# Feather_32U4_Servo_Board_V1_1.net
KiCad netlist of a schematic drawn in EAGLE
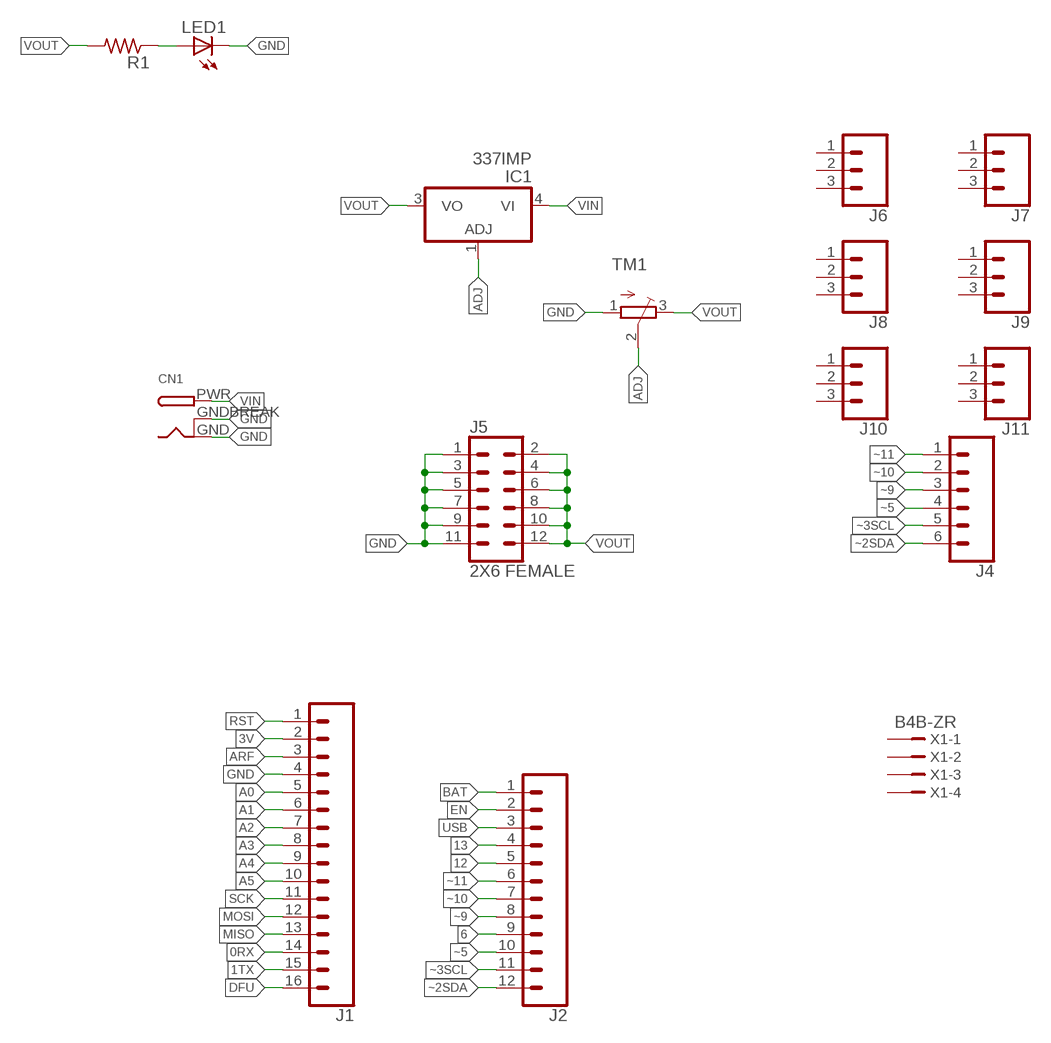
[diagram p0: schematic, sheet 1]

(export (version "E")
  (design (tool "Eeschema 10.0.6"))
  (components
    (comp (ref "CN1")
      (value "DCBARRELPTH")
      (footprint "eagle-import:DCJACK_2MM_PTH")
      (libsource (lib "eagle-import") (part "DCBARRELPTH"))
    )
    (comp (ref "IC1")
      (value "337IMP")
      (footprint "eagle-import:SOT223")
      (libsource (lib "eagle-import") (part "337IMP"))
    )
    (comp (ref "J1")
      (value "CONN_16")
      (footprint "eagle-import:1X16")
      (libsource (lib "eagle-import") (part "CONN_16"))
    )
    (comp (ref "J2")
      (value "CONN_12")
      (footprint "eagle-import:1X12")
      (libsource (lib "eagle-import") (part "CONN_12"))
    )
    (comp (ref "J4")
      (value "CONN_06SILK_FEMALE_PTH")
      (footprint "eagle-import:1X06")
      (libsource (lib "eagle-import") (part "CONN_06SILK_FEMALE_PTH"))
    )
    (comp (ref "J5")
      (value "2X6 FEMALE")
      (footprint "eagle-import:2X6")
      (libsource (lib "eagle-import") (part "CONN_06X2PTH_FEMALE"))
    )
    (comp (ref "J6")
      (value "CONN_03POLAR")
      (footprint "eagle-import:MOLEX-1X3")
      (libsource (lib "eagle-import") (part "CONN_03POLAR"))
    )
    (comp (ref "J7")
      (value "CONN_03POLAR")
      (footprint "eagle-import:MOLEX-1X3")
      (libsource (lib "eagle-import") (part "CONN_03POLAR"))
    )
    (comp (ref "J8")
      (value "CONN_03POLAR")
      (footprint "eagle-import:MOLEX-1X3")
      (libsource (lib "eagle-import") (part "CONN_03POLAR"))
    )
    (comp (ref "J9")
      (value "CONN_03POLAR")
      (footprint "eagle-import:MOLEX-1X3")
      (libsource (lib "eagle-import") (part "CONN_03POLAR"))
    )
    (comp (ref "J10")
      (value "CONN_03POLAR")
      (footprint "eagle-import:MOLEX-1X3")
      (libsource (lib "eagle-import") (part "CONN_03POLAR"))
    )
    (comp (ref "J11")
      (value "CONN_03POLAR")
      (footprint "eagle-import:MOLEX-1X3")
      (libsource (lib "eagle-import") (part "CONN_03POLAR"))
    )
    (comp (ref "LED1")
      (value "LEDCHIPLED_0805")
      (footprint "eagle-import:CHIPLED_0805")
      (libsource (lib "eagle-import") (part "LEDCHIPLED_0805"))
    )
    (comp (ref "R1")
      (value "R-US_M0805")
      (footprint "eagle-import:M0805")
      (libsource (lib "eagle-import") (part "R-US_M0805"))
    )
    (comp (ref "TM1")
      (value "TRIMPOTTC33X")
      (footprint "eagle-import:TC33X")
      (libsource (lib "eagle-import") (part "TRIMPOTTC33X"))
    )
    (comp (ref "X1")
      (value "B4B-ZR")
      (footprint "eagle-import:B4B-ZR")
      (libsource (lib "eagle-import") (part "?4B-ZRB"))
    )
  )
  (nets
    (net (code "1") (name "/~{2SDA}") (class "Default")
      (node (ref "J2") (pin "12") (pinfunction "12_12") (pintype "passive"))
      (node (ref "J4") (pin "6") (pinfunction "6_6") (pintype "passive"))
    )
    (net (code "2") (name "/~{3SCL}") (class "Default")
      (node (ref "J2") (pin "11") (pinfunction "11_11") (pintype "passive"))
      (node (ref "J4") (pin "5") (pinfunction "5_5") (pintype "passive"))
    )
    (net (code "3") (name "/~{5}") (class "Default")
      (node (ref "J2") (pin "10") (pinfunction "10_10") (pintype "passive"))
      (node (ref "J4") (pin "4") (pinfunction "4_4") (pintype "passive"))
    )
    (net (code "4") (name "/~{9}") (class "Default")
      (node (ref "J2") (pin "8") (pinfunction "8_8") (pintype "passive"))
      (node (ref "J4") (pin "3") (pinfunction "3_3") (pintype "passive"))
    )
    (net (code "5") (name "/~{10}") (class "Default")
      (node (ref "J2") (pin "7") (pinfunction "7_7") (pintype "passive"))
      (node (ref "J4") (pin "2") (pinfunction "2_2") (pintype "passive"))
    )
    (net (code "6") (name "/~{11}") (class "Default")
      (node (ref "J2") (pin "6") (pinfunction "6_6") (pintype "passive"))
      (node (ref "J4") (pin "1") (pinfunction "1_1") (pintype "passive"))
    )
    (net (code "7") (name "0RX") (class "Default")
      (node (ref "J1") (pin "14") (pinfunction "14_14") (pintype "passive"))
    )
    (net (code "8") (name "1TX") (class "Default")
      (node (ref "J1") (pin "15") (pinfunction "15_15") (pintype "passive"))
    )
    (net (code "9") (name "3V") (class "Default")
      (node (ref "J1") (pin "2") (pinfunction "2_2") (pintype "passive"))
    )
    (net (code "10") (name "6") (class "Default")
      (node (ref "J2") (pin "9") (pinfunction "9_9") (pintype "passive"))
    )
    (net (code "11") (name "12") (class "Default")
      (node (ref "J2") (pin "5") (pinfunction "5_5") (pintype "passive"))
    )
    (net (code "12") (name "13") (class "Default")
      (node (ref "J2") (pin "4") (pinfunction "4_4") (pintype "passive"))
    )
    (net (code "13") (name "A0") (class "Default")
      (node (ref "J1") (pin "5") (pinfunction "5_5") (pintype "passive"))
    )
    (net (code "14") (name "A1") (class "Default")
      (node (ref "J1") (pin "6") (pinfunction "6_6") (pintype "passive"))
    )
    (net (code "15") (name "A2") (class "Default")
      (node (ref "J1") (pin "7") (pinfunction "7_7") (pintype "passive"))
    )
    (net (code "16") (name "A3") (class "Default")
      (node (ref "J1") (pin "8") (pinfunction "8_8") (pintype "passive"))
    )
    (net (code "17") (name "A4") (class "Default")
      (node (ref "J1") (pin "9") (pinfunction "9_9") (pintype "passive"))
    )
    (net (code "18") (name "A5") (class "Default")
      (node (ref "J1") (pin "10") (pinfunction "10_10") (pintype "passive"))
    )
    (net (code "19") (name "ADJ") (class "Default")
      (node (ref "IC1") (pin "1") (pinfunction "ADJ_1") (pintype "input"))
      (node (ref "TM1") (pin "2") (pinfunction "S_2") (pintype "passive"))
    )
    (net (code "20") (name "ARF") (class "Default")
      (node (ref "J1") (pin "3") (pinfunction "3_3") (pintype "passive"))
    )
    (net (code "21") (name "BAT") (class "Default")
      (node (ref "J2") (pin "1") (pinfunction "1_1") (pintype "passive"))
    )
    (net (code "22") (name "DFU") (class "Default")
      (node (ref "J1") (pin "16") (pinfunction "16_16") (pintype "passive"))
    )
    (net (code "23") (name "EN") (class "Default")
      (node (ref "J2") (pin "2") (pinfunction "2_2") (pintype "passive"))
    )
    (net (code "24") (name "GND") (class "Default")
      (node (ref "CN1") (pin "GND") (pinfunction "GND_GND") (pintype "power_in"))
      (node (ref "CN1") (pin "GNDBREAK") (pinfunction "GNDBREAK_GNDBREAK") (pintype "power_in"))
      (node (ref "J1") (pin "4") (pinfunction "4_4") (pintype "passive"))
      (node (ref "J5") (pin "1") (pinfunction "1_1") (pintype "passive"))
      (node (ref "J5") (pin "11") (pinfunction "11_11") (pintype "passive"))
      (node (ref "J5") (pin "3") (pinfunction "3_3") (pintype "passive"))
      (node (ref "J5") (pin "5") (pinfunction "5_5") (pintype "passive"))
      (node (ref "J5") (pin "7") (pinfunction "7_7") (pintype "passive"))
      (node (ref "J5") (pin "9") (pinfunction "9_9") (pintype "passive"))
      (node (ref "LED1") (pin "C") (pinfunction "C_C") (pintype "passive"))
      (node (ref "TM1") (pin "1") (pinfunction "A_1") (pintype "passive"))
    )
    (net (code "25") (name "MISO") (class "Default")
      (node (ref "J1") (pin "13") (pinfunction "13_13") (pintype "passive"))
    )
    (net (code "26") (name "MOSI") (class "Default")
      (node (ref "J1") (pin "12") (pinfunction "12_12") (pintype "passive"))
    )
    (net (code "27") (name "Net-(LED1-PadA)") (class "Default")
      (node (ref "LED1") (pin "A") (pinfunction "A_A") (pintype "passive"))
      (node (ref "R1") (pin "1") (pinfunction "1_1") (pintype "passive"))
    )
    (net (code "28") (name "RST") (class "Default")
      (node (ref "J1") (pin "1") (pinfunction "1_1") (pintype "passive"))
    )
    (net (code "29") (name "SCK") (class "Default")
      (node (ref "J1") (pin "11") (pinfunction "11_11") (pintype "passive"))
    )
    (net (code "30") (name "USB") (class "Default")
      (node (ref "J2") (pin "3") (pinfunction "3_3") (pintype "passive"))
    )
    (net (code "31") (name "VIN") (class "Default")
      (node (ref "CN1") (pin "PWR") (pinfunction "PWR_PWR") (pintype "power_in"))
      (node (ref "IC1") (pin "4") (pinfunction "VI_4") (pintype "input"))
    )
    (net (code "32") (name "VOUT") (class "Default")
      (node (ref "IC1") (pin "3") (pinfunction "VO_3") (pintype "passive"))
      (node (ref "J5") (pin "10") (pinfunction "10_10") (pintype "passive"))
      (node (ref "J5") (pin "12") (pinfunction "12_12") (pintype "passive"))
      (node (ref "J5") (pin "2") (pinfunction "2_2") (pintype "passive"))
      (node (ref "J5") (pin "4") (pinfunction "4_4") (pintype "passive"))
      (node (ref "J5") (pin "6") (pinfunction "6_6") (pintype "passive"))
      (node (ref "J5") (pin "8") (pinfunction "8_8") (pintype "passive"))
      (node (ref "R1") (pin "2") (pinfunction "2_2") (pintype "passive"))
      (node (ref "TM1") (pin "3") (pinfunction "E_3") (pintype "passive"))
    )
    (net (code "33") (name "unconnected-(J6-Pad1)") (class "Default")
      (node (ref "J6") (pin "1") (pinfunction "1_1") (pintype "passive"))
    )
    (net (code "34") (name "unconnected-(J6-Pad2)") (class "Default")
      (node (ref "J6") (pin "2") (pinfunction "2_2") (pintype "passive"))
    )
    (net (code "35") (name "unconnected-(J6-Pad3)") (class "Default")
      (node (ref "J6") (pin "3") (pinfunction "3_3") (pintype "passive"))
    )
    (net (code "36") (name "unconnected-(J7-Pad1)") (class "Default")
      (node (ref "J7") (pin "1") (pinfunction "1_1") (pintype "passive"))
    )
    (net (code "37") (name "unconnected-(J7-Pad2)") (class "Default")
      (node (ref "J7") (pin "2") (pinfunction "2_2") (pintype "passive"))
    )
    (net (code "38") (name "unconnected-(J7-Pad3)") (class "Default")
      (node (ref "J7") (pin "3") (pinfunction "3_3") (pintype "passive"))
    )
    (net (code "39") (name "unconnected-(J8-Pad1)") (class "Default")
      (node (ref "J8") (pin "1") (pinfunction "1_1") (pintype "passive"))
    )
    (net (code "40") (name "unconnected-(J8-Pad2)") (class "Default")
      (node (ref "J8") (pin "2") (pinfunction "2_2") (pintype "passive"))
    )
    (net (code "41") (name "unconnected-(J8-Pad3)") (class "Default")
      (node (ref "J8") (pin "3") (pinfunction "3_3") (pintype "passive"))
    )
    (net (code "42") (name "unconnected-(J9-Pad1)") (class "Default")
      (node (ref "J9") (pin "1") (pinfunction "1_1") (pintype "passive"))
    )
    (net (code "43") (name "unconnected-(J9-Pad2)") (class "Default")
      (node (ref "J9") (pin "2") (pinfunction "2_2") (pintype "passive"))
    )
    (net (code "44") (name "unconnected-(J9-Pad3)") (class "Default")
      (node (ref "J9") (pin "3") (pinfunction "3_3") (pintype "passive"))
    )
    (net (code "45") (name "unconnected-(J10-Pad1)") (class "Default")
      (node (ref "J10") (pin "1") (pinfunction "1_1") (pintype "passive"))
    )
    (net (code "46") (name "unconnected-(J10-Pad2)") (class "Default")
      (node (ref "J10") (pin "2") (pinfunction "2_2") (pintype "passive"))
    )
    (net (code "47") (name "unconnected-(J10-Pad3)") (class "Default")
      (node (ref "J10") (pin "3") (pinfunction "3_3") (pintype "passive"))
    )
    (net (code "48") (name "unconnected-(J11-Pad1)") (class "Default")
      (node (ref "J11") (pin "1") (pinfunction "1_1") (pintype "passive"))
    )
    (net (code "49") (name "unconnected-(J11-Pad2)") (class "Default")
      (node (ref "J11") (pin "2") (pinfunction "2_2") (pintype "passive"))
    )
    (net (code "50") (name "unconnected-(J11-Pad3)") (class "Default")
      (node (ref "J11") (pin "3") (pinfunction "3_3") (pintype "passive"))
    )
    (net (code "51") (name "unconnected-(X1-Pad1)") (class "Default")
      (node (ref "X1") (pin "1") (pinfunction "1_1") (pintype "passive"))
    )
    (net (code "52") (name "unconnected-(X1B-1-Pad2)") (class "Default")
      (node (ref "X1") (pin "2") (pinfunction "1_2") (pintype "passive"))
    )
    (net (code "53") (name "unconnected-(X1C-1-Pad3)") (class "Default")
      (node (ref "X1") (pin "3") (pinfunction "1_3") (pintype "passive"))
    )
    (net (code "54") (name "unconnected-(X1D-1-Pad4)") (class "Default")
      (node (ref "X1") (pin "4") (pinfunction "1_4") (pintype "passive"))
    )
  )
)
